# transceiver-v1.net
KiCad netlist of a schematic drawn in EAGLE
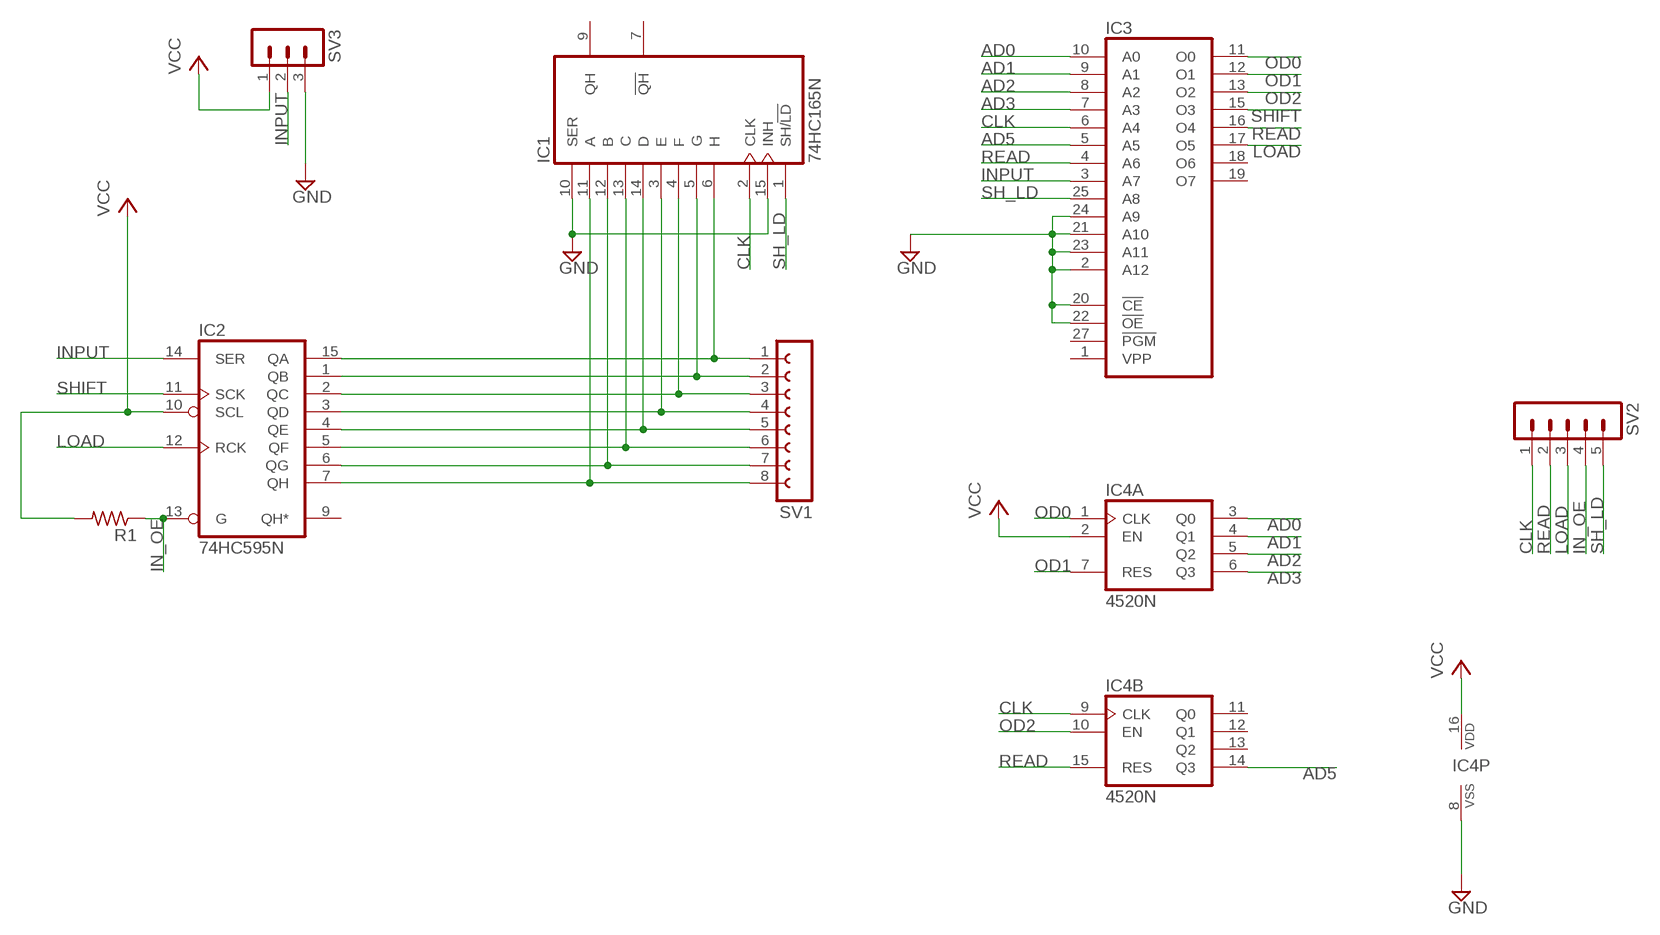
[diagram p0: schematic, sheet 1]

(export (version "E")
  (design (tool "Eeschema 10.0.6"))
  (components
    (comp (ref "IC1")
      (value "74HC165N")
      (footprint "eagle-import:DIL16")
      (libsource (lib "eagle-import") (part "74165NHC"))
    )
    (comp (ref "IC2")
      (value "74HC595N")
      (footprint "eagle-import:DIL16")
      (libsource (lib "eagle-import") (part "74595NHC"))
    )
    (comp (ref "IC3")
      (value "2764")
      (footprint "eagle-import:DIL28")
      (libsource (lib "eagle-import") (part "2764"))
    )
    (comp (ref "IC4")
      (value "4520N")
      (footprint "eagle-import:DIL16")
      (libsource (lib "eagle-import") (part "4520N"))
    )
    (comp (ref "R1")
      (value "R-US_0207/10")
      (footprint "eagle-import:0207_10")
      (libsource (lib "eagle-import") (part "R-US_0207/10"))
    )
    (comp (ref "SV1")
      (value "FE08-1")
      (footprint "eagle-import:FE08")
      (libsource (lib "eagle-import") (part "FE08-1"))
    )
    (comp (ref "SV2")
      (value "MA05-1")
      (footprint "eagle-import:MA05-1")
      (libsource (lib "eagle-import") (part "MA05-1"))
    )
    (comp (ref "SV3")
      (value "MA03-1")
      (footprint "eagle-import:MA03-1")
      (libsource (lib "eagle-import") (part "MA03-1"))
    )
  )
  (nets
    (net (code "1") (name "/AD0") (class "Default")
      (node (ref "IC3") (pin "10") (pinfunction "A0_10") (pintype "input"))
      (node (ref "IC4") (pin "3") (pinfunction "Q0_3") (pintype "output"))
    )
    (net (code "2") (name "/AD1") (class "Default")
      (node (ref "IC3") (pin "9") (pinfunction "A1_9") (pintype "input"))
      (node (ref "IC4") (pin "4") (pinfunction "Q1_4") (pintype "output"))
    )
    (net (code "3") (name "/AD2") (class "Default")
      (node (ref "IC3") (pin "8") (pinfunction "A2_8") (pintype "input"))
      (node (ref "IC4") (pin "5") (pinfunction "Q2_5") (pintype "output"))
    )
    (net (code "4") (name "/AD3") (class "Default")
      (node (ref "IC3") (pin "7") (pinfunction "A3_7") (pintype "input"))
      (node (ref "IC4") (pin "6") (pinfunction "Q3_6") (pintype "output"))
    )
    (net (code "5") (name "/AD5") (class "Default")
      (node (ref "IC3") (pin "5") (pinfunction "A5_5") (pintype "input"))
      (node (ref "IC4") (pin "14") (pinfunction "Q3_14") (pintype "output"))
    )
    (net (code "6") (name "/CLK") (class "Default")
      (node (ref "IC1") (pin "2") (pinfunction "CLK_2") (pintype "input"))
      (node (ref "IC3") (pin "6") (pinfunction "A4_6") (pintype "input"))
      (node (ref "IC4") (pin "9") (pinfunction "CLK_9") (pintype "input"))
      (node (ref "SV2") (pin "1") (pinfunction "1_1") (pintype "passive"))
    )
    (net (code "7") (name "/INPUT") (class "Default")
      (node (ref "IC2") (pin "14") (pinfunction "SER_14") (pintype "input"))
      (node (ref "IC3") (pin "3") (pinfunction "A7_3") (pintype "input"))
      (node (ref "SV3") (pin "2") (pinfunction "2_2") (pintype "passive"))
    )
    (net (code "8") (name "/IN_OE") (class "Default")
      (node (ref "IC2") (pin "13") (pinfunction "G_13") (pintype "input"))
      (node (ref "R1") (pin "1") (pinfunction "1_1") (pintype "passive"))
      (node (ref "SV2") (pin "4") (pinfunction "4_4") (pintype "passive"))
    )
    (net (code "9") (name "/LOAD") (class "Default")
      (node (ref "IC2") (pin "12") (pinfunction "RCK_12") (pintype "input"))
      (node (ref "IC3") (pin "17") (pinfunction "O5_17") (pintype "tri_state"))
      (node (ref "SV2") (pin "3") (pinfunction "3_3") (pintype "passive"))
    )
    (net (code "10") (name "/OD0") (class "Default")
      (node (ref "IC3") (pin "11") (pinfunction "O0_11") (pintype "tri_state"))
      (node (ref "IC4") (pin "1") (pinfunction "CLK_1") (pintype "input"))
    )
    (net (code "11") (name "/OD1") (class "Default")
      (node (ref "IC3") (pin "12") (pinfunction "O1_12") (pintype "tri_state"))
      (node (ref "IC4") (pin "7") (pinfunction "RES_7") (pintype "input"))
    )
    (net (code "12") (name "/OD2") (class "Default")
      (node (ref "IC3") (pin "13") (pinfunction "O2_13") (pintype "tri_state"))
      (node (ref "IC4") (pin "10") (pinfunction "EN_10") (pintype "input"))
    )
    (net (code "13") (name "/READ") (class "Default")
      (node (ref "IC3") (pin "16") (pinfunction "O4_16") (pintype "tri_state"))
      (node (ref "IC3") (pin "4") (pinfunction "A6_4") (pintype "input"))
      (node (ref "IC4") (pin "15") (pinfunction "RES_15") (pintype "input"))
      (node (ref "SV2") (pin "2") (pinfunction "2_2") (pintype "passive"))
    )
    (net (code "14") (name "/SHIFT") (class "Default")
      (node (ref "IC2") (pin "11") (pinfunction "SCK_11") (pintype "input"))
      (node (ref "IC3") (pin "15") (pinfunction "O3_15") (pintype "tri_state"))
    )
    (net (code "15") (name "/SH_LD") (class "Default")
      (node (ref "IC1") (pin "1") (pinfunction "SH/~{LD}_1") (pintype "input"))
      (node (ref "IC3") (pin "25") (pinfunction "A8_25") (pintype "input"))
      (node (ref "SV2") (pin "5") (pinfunction "5_5") (pintype "passive"))
    )
    (net (code "16") (name "GND") (class "Default")
      (node (ref "IC1") (pin "10") (pinfunction "SER_10") (pintype "input"))
      (node (ref "IC1") (pin "15") (pinfunction "INH_15") (pintype "input"))
      (node (ref "IC3") (pin "2") (pinfunction "A12_2") (pintype "input"))
      (node (ref "IC3") (pin "20") (pinfunction "~{CE}_20") (pintype "input"))
      (node (ref "IC3") (pin "21") (pinfunction "A10_21") (pintype "input"))
      (node (ref "IC3") (pin "22") (pinfunction "~{OE}_22") (pintype "input"))
      (node (ref "IC3") (pin "23") (pinfunction "A11_23") (pintype "input"))
      (node (ref "IC3") (pin "24") (pinfunction "A9_24") (pintype "input"))
      (node (ref "IC4") (pin "8") (pinfunction "VSS_8") (pintype "power_in"))
      (node (ref "SV3") (pin "3") (pinfunction "3_3") (pintype "passive"))
    )
    (net (code "17") (name "Net-(IC1A-A)") (class "Default")
      (node (ref "IC1") (pin "11") (pinfunction "A_11") (pintype "input"))
      (node (ref "IC2") (pin "7") (pinfunction "QH_7") (pintype "tri_state"))
      (node (ref "SV1") (pin "8") (pinfunction "8_8") (pintype "passive"))
    )
    (net (code "18") (name "Net-(IC1A-B)") (class "Default")
      (node (ref "IC1") (pin "12") (pinfunction "B_12") (pintype "input"))
      (node (ref "IC2") (pin "6") (pinfunction "QG_6") (pintype "tri_state"))
      (node (ref "SV1") (pin "7") (pinfunction "7_7") (pintype "passive"))
    )
    (net (code "19") (name "Net-(IC1A-C)") (class "Default")
      (node (ref "IC1") (pin "13") (pinfunction "C_13") (pintype "input"))
      (node (ref "IC2") (pin "5") (pinfunction "QF_5") (pintype "tri_state"))
      (node (ref "SV1") (pin "6") (pinfunction "6_6") (pintype "passive"))
    )
    (net (code "20") (name "Net-(IC1A-D)") (class "Default")
      (node (ref "IC1") (pin "14") (pinfunction "D_14") (pintype "input"))
      (node (ref "IC2") (pin "4") (pinfunction "QE_4") (pintype "tri_state"))
      (node (ref "SV1") (pin "5") (pinfunction "5_5") (pintype "passive"))
    )
    (net (code "21") (name "Net-(IC1A-E)") (class "Default")
      (node (ref "IC1") (pin "3") (pinfunction "E_3") (pintype "input"))
      (node (ref "IC2") (pin "3") (pinfunction "QD_3") (pintype "tri_state"))
      (node (ref "SV1") (pin "4") (pinfunction "4_4") (pintype "passive"))
    )
    (net (code "22") (name "Net-(IC1A-F)") (class "Default")
      (node (ref "IC1") (pin "4") (pinfunction "F_4") (pintype "input"))
      (node (ref "IC2") (pin "2") (pinfunction "QC_2") (pintype "tri_state"))
      (node (ref "SV1") (pin "3") (pinfunction "3_3") (pintype "passive"))
    )
    (net (code "23") (name "Net-(IC1A-G)") (class "Default")
      (node (ref "IC1") (pin "5") (pinfunction "G_5") (pintype "input"))
      (node (ref "IC2") (pin "1") (pinfunction "QB_1") (pintype "tri_state"))
      (node (ref "SV1") (pin "2") (pinfunction "2_2") (pintype "passive"))
    )
    (net (code "24") (name "Net-(IC1A-H)") (class "Default")
      (node (ref "IC1") (pin "6") (pinfunction "H_6") (pintype "input"))
      (node (ref "IC2") (pin "15") (pinfunction "QA_15") (pintype "tri_state"))
      (node (ref "SV1") (pin "1") (pinfunction "1_1") (pintype "passive"))
    )
    (net (code "25") (name "VCC") (class "Default")
      (node (ref "IC2") (pin "10") (pinfunction "SCL_10") (pintype "input"))
      (node (ref "IC4") (pin "16") (pinfunction "VDD_16") (pintype "power_in"))
      (node (ref "IC4") (pin "2") (pinfunction "EN_2") (pintype "input"))
      (node (ref "R1") (pin "2") (pinfunction "2_2") (pintype "passive"))
      (node (ref "SV3") (pin "1") (pinfunction "1_1") (pintype "passive"))
    )
    (net (code "26") (name "unconnected-(IC1A-QH-Pad9)") (class "Default")
      (node (ref "IC1") (pin "9") (pinfunction "QH_9") (pintype "output"))
    )
    (net (code "27") (name "unconnected-(IC1A-~{QH}-Pad7)") (class "Default")
      (node (ref "IC1") (pin "7") (pinfunction "~{QH}_7") (pintype "output"))
    )
    (net (code "28") (name "unconnected-(IC2A-QH*-Pad9)") (class "Default")
      (node (ref "IC2") (pin "9") (pinfunction "QH*_9") (pintype "tri_state"))
    )
    (net (code "29") (name "unconnected-(IC3A-O6-Pad18)") (class "Default")
      (node (ref "IC3") (pin "18") (pinfunction "O6_18") (pintype "tri_state"))
    )
    (net (code "30") (name "unconnected-(IC3A-O7-Pad19)") (class "Default")
      (node (ref "IC3") (pin "19") (pinfunction "O7_19") (pintype "tri_state"))
    )
    (net (code "31") (name "unconnected-(IC3A-VPP-Pad1)") (class "Default")
      (node (ref "IC3") (pin "1") (pinfunction "VPP_1") (pintype "input"))
    )
    (net (code "32") (name "unconnected-(IC3A-~{PGM}-Pad27)") (class "Default")
      (node (ref "IC3") (pin "27") (pinfunction "~{PGM}_27") (pintype "input"))
    )
    (net (code "33") (name "unconnected-(IC4B-Q0-Pad11)") (class "Default")
      (node (ref "IC4") (pin "11") (pinfunction "Q0_11") (pintype "output"))
    )
    (net (code "34") (name "unconnected-(IC4B-Q1-Pad12)") (class "Default")
      (node (ref "IC4") (pin "12") (pinfunction "Q1_12") (pintype "output"))
    )
    (net (code "35") (name "unconnected-(IC4B-Q2-Pad13)") (class "Default")
      (node (ref "IC4") (pin "13") (pinfunction "Q2_13") (pintype "output"))
    )
  )
)
